# QuizGame2.net
KiCad netlist of a schematic drawn in EAGLE
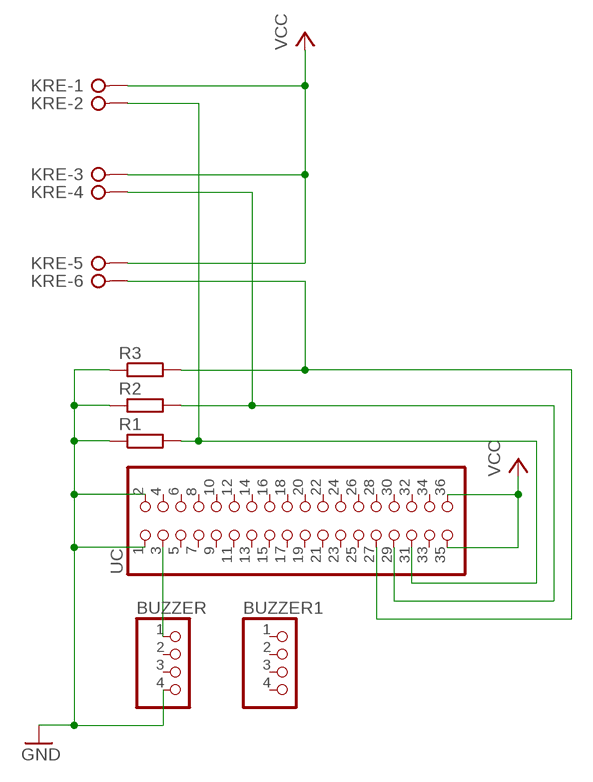
[diagram p0: schematic, sheet 1]

(export (version "E")
  (design (tool "Eeschema 10.0.6"))
  (components
    (comp (ref "BUZZER")
      (value "PINHD-1X4")
      (footprint "eagle-import:1X04")
      (libsource (lib "eagle-import") (part "PINHD-1X4"))
    )
    (comp (ref "BUZZER1")
      (value "PINHD-1X4")
      (footprint "eagle-import:1X04")
      (libsource (lib "eagle-import") (part "PINHD-1X4"))
    )
    (comp (ref "KRE")
      (value "W237-06P")
      (footprint "eagle-import:W237-6P")
      (libsource (lib "eagle-import") (part "W237-06P"))
    )
    (comp (ref "R1")
      (value "R-EU_0207/12")
      (footprint "eagle-import:0207_12")
      (libsource (lib "eagle-import") (part "R-EU_0207/12"))
    )
    (comp (ref "R2")
      (value "R-EU_0207/12")
      (footprint "eagle-import:0207_12")
      (libsource (lib "eagle-import") (part "R-EU_0207/12"))
    )
    (comp (ref "R3")
      (value "R-EU_0207/12")
      (footprint "eagle-import:0207_12")
      (libsource (lib "eagle-import") (part "R-EU_0207/12"))
    )
    (comp (ref "UC")
      (value "PINHD-2X18")
      (footprint "eagle-import:2X18")
      (libsource (lib "eagle-import") (part "PINHD-2X18"))
    )
  )
  (nets
    (net (code "1") (name "GND") (class "Default")
      (node (ref "BUZZER") (pin "4") (pinfunction "4_4") (pintype "passive"))
      (node (ref "R1") (pin "1") (pinfunction "1_1") (pintype "passive"))
      (node (ref "R2") (pin "1") (pinfunction "1_1") (pintype "passive"))
      (node (ref "R3") (pin "1") (pinfunction "1_1") (pintype "passive"))
      (node (ref "UC") (pin "1") (pinfunction "1_1") (pintype "passive"))
      (node (ref "UC") (pin "2") (pinfunction "2_2") (pintype "passive"))
    )
    (net (code "2") (name "Net-(BUZZER-Pad1)") (class "Default")
      (node (ref "BUZZER") (pin "1") (pinfunction "1_1") (pintype "passive"))
      (node (ref "UC") (pin "3") (pinfunction "3_3") (pintype "passive"))
    )
    (net (code "3") (name "Net-(KREB-KL)") (class "Default")
      (node (ref "KRE") (pin "2") (pinfunction "KL_2") (pintype "passive"))
      (node (ref "R1") (pin "2") (pinfunction "2_2") (pintype "passive"))
      (node (ref "UC") (pin "31") (pinfunction "31_31") (pintype "passive"))
    )
    (net (code "4") (name "Net-(KRED-KL)") (class "Default")
      (node (ref "KRE") (pin "4") (pinfunction "KL_4") (pintype "passive"))
      (node (ref "R2") (pin "2") (pinfunction "2_2") (pintype "passive"))
      (node (ref "UC") (pin "29") (pinfunction "29_29") (pintype "passive"))
    )
    (net (code "5") (name "Net-(KREF-KL)") (class "Default")
      (node (ref "KRE") (pin "6") (pinfunction "KL_6") (pintype "passive"))
      (node (ref "R3") (pin "2") (pinfunction "2_2") (pintype "passive"))
      (node (ref "UC") (pin "27") (pinfunction "27_27") (pintype "passive"))
    )
    (net (code "6") (name "VCC") (class "Default")
      (node (ref "KRE") (pin "1") (pinfunction "KL_1") (pintype "passive"))
      (node (ref "KRE") (pin "3") (pinfunction "KL_3") (pintype "passive"))
      (node (ref "KRE") (pin "5") (pinfunction "KL_5") (pintype "passive"))
      (node (ref "UC") (pin "35") (pinfunction "35_35") (pintype "passive"))
      (node (ref "UC") (pin "36") (pinfunction "36_36") (pintype "passive"))
    )
    (net (code "7") (name "unconnected-(BUZZER-Pad2)") (class "Default")
      (node (ref "BUZZER") (pin "2") (pinfunction "2_2") (pintype "passive"))
    )
    (net (code "8") (name "unconnected-(BUZZER-Pad3)") (class "Default")
      (node (ref "BUZZER") (pin "3") (pinfunction "3_3") (pintype "passive"))
    )
    (net (code "9") (name "unconnected-(BUZZER1-Pad1)") (class "Default")
      (node (ref "BUZZER1") (pin "1") (pinfunction "1_1") (pintype "passive"))
    )
    (net (code "10") (name "unconnected-(BUZZER1-Pad2)") (class "Default")
      (node (ref "BUZZER1") (pin "2") (pinfunction "2_2") (pintype "passive"))
    )
    (net (code "11") (name "unconnected-(BUZZER1-Pad3)") (class "Default")
      (node (ref "BUZZER1") (pin "3") (pinfunction "3_3") (pintype "passive"))
    )
    (net (code "12") (name "unconnected-(BUZZER1-Pad4)") (class "Default")
      (node (ref "BUZZER1") (pin "4") (pinfunction "4_4") (pintype "passive"))
    )
    (net (code "13") (name "unconnected-(UC-Pad4)") (class "Default")
      (node (ref "UC") (pin "4") (pinfunction "4_4") (pintype "passive"))
    )
    (net (code "14") (name "unconnected-(UC-Pad5)") (class "Default")
      (node (ref "UC") (pin "5") (pinfunction "5_5") (pintype "passive"))
    )
    (net (code "15") (name "unconnected-(UC-Pad6)") (class "Default")
      (node (ref "UC") (pin "6") (pinfunction "6_6") (pintype "passive"))
    )
    (net (code "16") (name "unconnected-(UC-Pad7)") (class "Default")
      (node (ref "UC") (pin "7") (pinfunction "7_7") (pintype "passive"))
    )
    (net (code "17") (name "unconnected-(UC-Pad8)") (class "Default")
      (node (ref "UC") (pin "8") (pinfunction "8_8") (pintype "passive"))
    )
    (net (code "18") (name "unconnected-(UC-Pad9)") (class "Default")
      (node (ref "UC") (pin "9") (pinfunction "9_9") (pintype "passive"))
    )
    (net (code "19") (name "unconnected-(UC-Pad10)") (class "Default")
      (node (ref "UC") (pin "10") (pinfunction "10_10") (pintype "passive"))
    )
    (net (code "20") (name "unconnected-(UC-Pad11)") (class "Default")
      (node (ref "UC") (pin "11") (pinfunction "11_11") (pintype "passive"))
    )
    (net (code "21") (name "unconnected-(UC-Pad12)") (class "Default")
      (node (ref "UC") (pin "12") (pinfunction "12_12") (pintype "passive"))
    )
    (net (code "22") (name "unconnected-(UC-Pad13)") (class "Default")
      (node (ref "UC") (pin "13") (pinfunction "13_13") (pintype "passive"))
    )
    (net (code "23") (name "unconnected-(UC-Pad14)") (class "Default")
      (node (ref "UC") (pin "14") (pinfunction "14_14") (pintype "passive"))
    )
    (net (code "24") (name "unconnected-(UC-Pad15)") (class "Default")
      (node (ref "UC") (pin "15") (pinfunction "15_15") (pintype "passive"))
    )
    (net (code "25") (name "unconnected-(UC-Pad16)") (class "Default")
      (node (ref "UC") (pin "16") (pinfunction "16_16") (pintype "passive"))
    )
    (net (code "26") (name "unconnected-(UC-Pad17)") (class "Default")
      (node (ref "UC") (pin "17") (pinfunction "17_17") (pintype "passive"))
    )
    (net (code "27") (name "unconnected-(UC-Pad18)") (class "Default")
      (node (ref "UC") (pin "18") (pinfunction "18_18") (pintype "passive"))
    )
    (net (code "28") (name "unconnected-(UC-Pad19)") (class "Default")
      (node (ref "UC") (pin "19") (pinfunction "19_19") (pintype "passive"))
    )
    (net (code "29") (name "unconnected-(UC-Pad20)") (class "Default")
      (node (ref "UC") (pin "20") (pinfunction "20_20") (pintype "passive"))
    )
    (net (code "30") (name "unconnected-(UC-Pad21)") (class "Default")
      (node (ref "UC") (pin "21") (pinfunction "21_21") (pintype "passive"))
    )
    (net (code "31") (name "unconnected-(UC-Pad22)") (class "Default")
      (node (ref "UC") (pin "22") (pinfunction "22_22") (pintype "passive"))
    )
    (net (code "32") (name "unconnected-(UC-Pad23)") (class "Default")
      (node (ref "UC") (pin "23") (pinfunction "23_23") (pintype "passive"))
    )
    (net (code "33") (name "unconnected-(UC-Pad24)") (class "Default")
      (node (ref "UC") (pin "24") (pinfunction "24_24") (pintype "passive"))
    )
    (net (code "34") (name "unconnected-(UC-Pad25)") (class "Default")
      (node (ref "UC") (pin "25") (pinfunction "25_25") (pintype "passive"))
    )
    (net (code "35") (name "unconnected-(UC-Pad26)") (class "Default")
      (node (ref "UC") (pin "26") (pinfunction "26_26") (pintype "passive"))
    )
    (net (code "36") (name "unconnected-(UC-Pad28)") (class "Default")
      (node (ref "UC") (pin "28") (pinfunction "28_28") (pintype "passive"))
    )
    (net (code "37") (name "unconnected-(UC-Pad30)") (class "Default")
      (node (ref "UC") (pin "30") (pinfunction "30_30") (pintype "passive"))
    )
    (net (code "38") (name "unconnected-(UC-Pad32)") (class "Default")
      (node (ref "UC") (pin "32") (pinfunction "32_32") (pintype "passive"))
    )
    (net (code "39") (name "unconnected-(UC-Pad33)") (class "Default")
      (node (ref "UC") (pin "33") (pinfunction "33_33") (pintype "passive"))
    )
    (net (code "40") (name "unconnected-(UC-Pad34)") (class "Default")
      (node (ref "UC") (pin "34") (pinfunction "34_34") (pintype "passive"))
    )
  )
)
